# VOLTAGE_MEASURE.net
KiCad netlist of a schematic drawn in Altium Designer
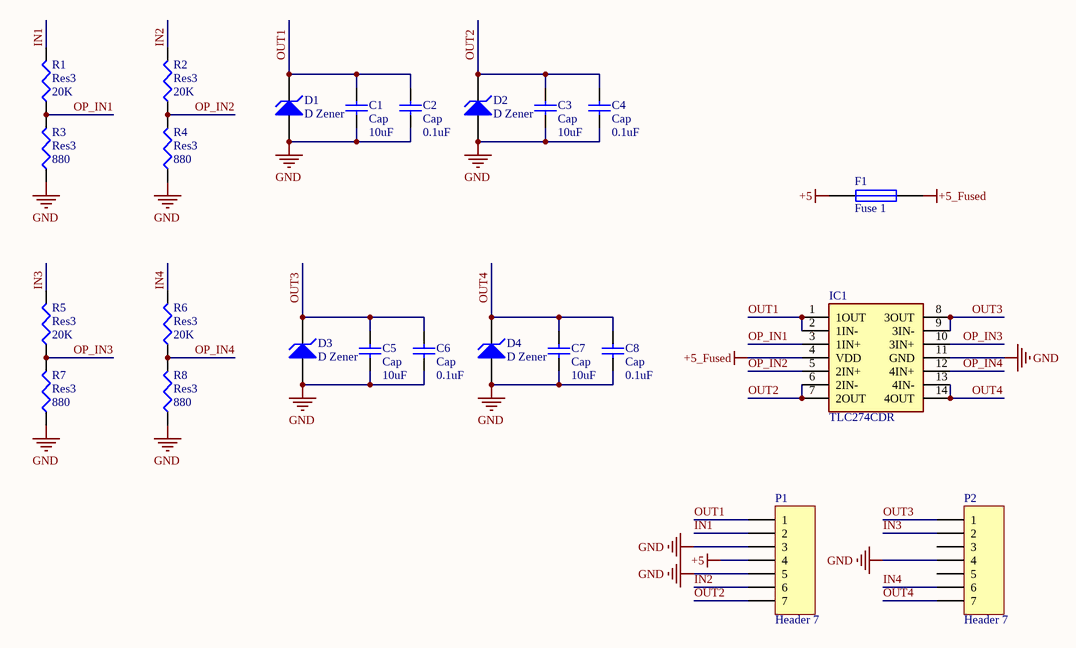
[diagram p0: VOLTAGE_MEASURE.SchDoc]

(export (version "E")
  (design (tool "Eeschema 10.0.6"))
  (components
    (comp (ref "C1")
      (value "Cap")
      (footprint "C1206")
      (description "Capacitor")
      (fields (field (name "ALTIUM_VALUE") "10uF") (field (name "PUBLISHER") "Altium Limited"))
      (libsource (lib "Miscellaneous Devices") (part "Cap"))
    )
    (comp (ref "C2")
      (value "Cap")
      (footprint "1608[0603]")
      (description "Capacitor")
      (fields (field (name "ALTIUM_VALUE") "0.1uF") (field (name "PUBLISHER") "Altium Limited"))
      (libsource (lib "Miscellaneous Devices") (part "Cap"))
    )
    (comp (ref "C3")
      (value "Cap")
      (footprint "C1206")
      (description "Capacitor")
      (fields (field (name "ALTIUM_VALUE") "10uF") (field (name "PUBLISHER") "Altium Limited"))
      (libsource (lib "Miscellaneous Devices") (part "Cap"))
    )
    (comp (ref "C4")
      (value "Cap")
      (footprint "1608[0603]")
      (description "Capacitor")
      (fields (field (name "ALTIUM_VALUE") "0.1uF") (field (name "PUBLISHER") "Altium Limited"))
      (libsource (lib "Miscellaneous Devices") (part "Cap"))
    )
    (comp (ref "C5")
      (value "Cap")
      (footprint "C1206")
      (description "Capacitor")
      (fields (field (name "ALTIUM_VALUE") "10uF") (field (name "PUBLISHER") "Altium Limited"))
      (libsource (lib "Miscellaneous Devices") (part "Cap"))
    )
    (comp (ref "C6")
      (value "Cap")
      (footprint "1608[0603]")
      (description "Capacitor")
      (fields (field (name "ALTIUM_VALUE") "0.1uF") (field (name "PUBLISHER") "Altium Limited"))
      (libsource (lib "Miscellaneous Devices") (part "Cap"))
    )
    (comp (ref "C7")
      (value "Cap")
      (footprint "C1206")
      (description "Capacitor")
      (fields (field (name "ALTIUM_VALUE") "10uF") (field (name "PUBLISHER") "Altium Limited"))
      (libsource (lib "Miscellaneous Devices") (part "Cap"))
    )
    (comp (ref "C8")
      (value "Cap")
      (footprint "1608[0603]")
      (description "Capacitor")
      (fields (field (name "ALTIUM_VALUE") "0.1uF") (field (name "PUBLISHER") "Altium Limited"))
      (libsource (lib "Miscellaneous Devices") (part "Cap"))
    )
    (comp (ref "D1")
      (value "D Zener")
      (footprint "C1206")
      (description "Zener Diode")
      (fields (field (name "PUBLISHER") "Altium Limited"))
      (libsource (lib "Miscellaneous Devices") (part "D Zener"))
    )
    (comp (ref "D2")
      (value "D Zener")
      (footprint "C1206")
      (description "Zener Diode")
      (fields (field (name "PUBLISHER") "Altium Limited"))
      (libsource (lib "Miscellaneous Devices") (part "D Zener"))
    )
    (comp (ref "D3")
      (value "D Zener")
      (footprint "C1206")
      (description "Zener Diode")
      (fields (field (name "PUBLISHER") "Altium Limited"))
      (libsource (lib "Miscellaneous Devices") (part "D Zener"))
    )
    (comp (ref "D4")
      (value "D Zener")
      (footprint "C1206")
      (description "Zener Diode")
      (fields (field (name "PUBLISHER") "Altium Limited"))
      (libsource (lib "Miscellaneous Devices") (part "D Zener"))
    )
    (comp (ref "F1")
      (value "Fuse 1")
      (footprint "C1206")
      (description "Fuse")
      (fields (field (name "PUBLISHER") "Altium Limited"))
      (libsource (lib "Miscellaneous Devices") (part "Fuse 1"))
    )
    (comp (ref "IC1")
      (value "TLC274CDR")
      (footprint "SamacSys:SOIC127P600X175-14N")
      (description "Integrated Circuit")
      (fields (field (name "MOUSER PART NUMBER") "595-TLC274CDR") (field (name "RS PART NUMBER") "0527237"))
      (libsource (lib "*") (part "TLC274CDR"))
    )
    (comp (ref "P1")
      (value "Header 7")
      (footprint "HDR1X7")
      (description "Header, 7-Pin")
      (fields (field (name "PUBLISHER") "Altium Limited"))
      (libsource (lib "Miscellaneous Connectors") (part "Header 7"))
    )
    (comp (ref "P2")
      (value "Header 7")
      (footprint "HDR1X7")
      (description "Header, 7-Pin")
      (fields (field (name "PUBLISHER") "Altium Limited"))
      (libsource (lib "Miscellaneous Connectors") (part "Header 7"))
    )
    (comp (ref "R1")
      (value "Res3")
      (footprint "J1-0603")
      (description "Resistor")
      (fields (field (name "ALTIUM_VALUE") "20K") (field (name "PUBLISHER") "Altium Limited"))
      (libsource (lib "Miscellaneous Devices") (part "Res3"))
    )
    (comp (ref "R2")
      (value "Res3")
      (footprint "J1-0603")
      (description "Resistor")
      (fields (field (name "ALTIUM_VALUE") "20K") (field (name "PUBLISHER") "Altium Limited"))
      (libsource (lib "Miscellaneous Devices") (part "Res3"))
    )
    (comp (ref "R3")
      (value "Res3")
      (footprint "J1-0603")
      (description "Resistor")
      (fields (field (name "ALTIUM_VALUE") "880") (field (name "PUBLISHER") "Altium Limited"))
      (libsource (lib "Miscellaneous Devices") (part "Res3"))
    )
    (comp (ref "R4")
      (value "Res3")
      (footprint "J1-0603")
      (description "Resistor")
      (fields (field (name "ALTIUM_VALUE") "880") (field (name "PUBLISHER") "Altium Limited"))
      (libsource (lib "Miscellaneous Devices") (part "Res3"))
    )
    (comp (ref "R5")
      (value "Res3")
      (footprint "J1-0603")
      (description "Resistor")
      (fields (field (name "ALTIUM_VALUE") "20K") (field (name "PUBLISHER") "Altium Limited"))
      (libsource (lib "Miscellaneous Devices") (part "Res3"))
    )
    (comp (ref "R6")
      (value "Res3")
      (footprint "J1-0603")
      (description "Resistor")
      (fields (field (name "ALTIUM_VALUE") "20K") (field (name "PUBLISHER") "Altium Limited"))
      (libsource (lib "Miscellaneous Devices") (part "Res3"))
    )
    (comp (ref "R7")
      (value "Res3")
      (footprint "J1-0603")
      (description "Resistor")
      (fields (field (name "ALTIUM_VALUE") "880") (field (name "PUBLISHER") "Altium Limited"))
      (libsource (lib "Miscellaneous Devices") (part "Res3"))
    )
    (comp (ref "R8")
      (value "Res3")
      (footprint "J1-0603")
      (description "Resistor")
      (fields (field (name "ALTIUM_VALUE") "880") (field (name "PUBLISHER") "Altium Limited"))
      (libsource (lib "Miscellaneous Devices") (part "Res3"))
    )
  )
  (nets
    (net (code "1") (name "+5") (class "Default")
      (node (ref "F1") (pin "2") (pinfunction "2_2") (pintype "passive"))
      (node (ref "P1") (pin "4") (pinfunction "4_4") (pintype "passive"))
    )
    (net (code "2") (name "+5_Fused") (class "Default")
      (node (ref "F1") (pin "1") (pinfunction "1_1") (pintype "passive"))
      (node (ref "IC1") (pin "4") (pinfunction "VDD_4") (pintype "passive"))
    )
    (net (code "3") (name "/IN1") (class "Default")
      (node (ref "P1") (pin "2") (pinfunction "2_2") (pintype "passive"))
      (node (ref "R1") (pin "2") (pinfunction "2_2") (pintype "passive"))
    )
    (net (code "4") (name "/IN2") (class "Default")
      (node (ref "P1") (pin "6") (pinfunction "6_6") (pintype "passive"))
      (node (ref "R2") (pin "2") (pinfunction "2_2") (pintype "passive"))
    )
    (net (code "5") (name "/IN3") (class "Default")
      (node (ref "P2") (pin "2") (pinfunction "2_2") (pintype "passive"))
      (node (ref "R5") (pin "2") (pinfunction "2_2") (pintype "passive"))
    )
    (net (code "6") (name "/IN4") (class "Default")
      (node (ref "P2") (pin "6") (pinfunction "6_6") (pintype "passive"))
      (node (ref "R6") (pin "2") (pinfunction "2_2") (pintype "passive"))
    )
    (net (code "7") (name "/OP_IN1") (class "Default")
      (node (ref "IC1") (pin "3") (pinfunction "1IN+_3") (pintype "passive"))
      (node (ref "R1") (pin "1") (pinfunction "1_1") (pintype "passive"))
      (node (ref "R3") (pin "2") (pinfunction "2_2") (pintype "passive"))
    )
    (net (code "8") (name "/OP_IN2") (class "Default")
      (node (ref "IC1") (pin "5") (pinfunction "2IN+_5") (pintype "passive"))
      (node (ref "R2") (pin "1") (pinfunction "1_1") (pintype "passive"))
      (node (ref "R4") (pin "2") (pinfunction "2_2") (pintype "passive"))
    )
    (net (code "9") (name "/OP_IN3") (class "Default")
      (node (ref "IC1") (pin "10") (pinfunction "3IN+_10") (pintype "passive"))
      (node (ref "R5") (pin "1") (pinfunction "1_1") (pintype "passive"))
      (node (ref "R7") (pin "2") (pinfunction "2_2") (pintype "passive"))
    )
    (net (code "10") (name "/OP_IN4") (class "Default")
      (node (ref "IC1") (pin "12") (pinfunction "4IN+_12") (pintype "passive"))
      (node (ref "R6") (pin "1") (pinfunction "1_1") (pintype "passive"))
      (node (ref "R8") (pin "2") (pinfunction "2_2") (pintype "passive"))
    )
    (net (code "11") (name "/OUT1") (class "Default")
      (node (ref "C1") (pin "2") (pinfunction "2_2") (pintype "passive"))
      (node (ref "C2") (pin "2") (pinfunction "2_2") (pintype "passive"))
      (node (ref "D1") (pin "2") (pinfunction "K_2") (pintype "passive"))
      (node (ref "IC1") (pin "1") (pinfunction "1OUT_1") (pintype "passive"))
      (node (ref "IC1") (pin "2") (pinfunction "1IN-_2") (pintype "passive"))
      (node (ref "P1") (pin "1") (pinfunction "1_1") (pintype "passive"))
    )
    (net (code "12") (name "/OUT2") (class "Default")
      (node (ref "C3") (pin "2") (pinfunction "2_2") (pintype "passive"))
      (node (ref "C4") (pin "2") (pinfunction "2_2") (pintype "passive"))
      (node (ref "D2") (pin "2") (pinfunction "K_2") (pintype "passive"))
      (node (ref "IC1") (pin "6") (pinfunction "2IN-_6") (pintype "passive"))
      (node (ref "IC1") (pin "7") (pinfunction "2OUT_7") (pintype "passive"))
      (node (ref "P1") (pin "7") (pinfunction "7_7") (pintype "passive"))
    )
    (net (code "13") (name "/OUT3") (class "Default")
      (node (ref "C5") (pin "2") (pinfunction "2_2") (pintype "passive"))
      (node (ref "C6") (pin "2") (pinfunction "2_2") (pintype "passive"))
      (node (ref "D3") (pin "2") (pinfunction "K_2") (pintype "passive"))
      (node (ref "IC1") (pin "8") (pinfunction "3OUT_8") (pintype "passive"))
      (node (ref "IC1") (pin "9") (pinfunction "3IN-_9") (pintype "passive"))
      (node (ref "P2") (pin "1") (pinfunction "1_1") (pintype "passive"))
    )
    (net (code "14") (name "/OUT4") (class "Default")
      (node (ref "C7") (pin "2") (pinfunction "2_2") (pintype "passive"))
      (node (ref "C8") (pin "2") (pinfunction "2_2") (pintype "passive"))
      (node (ref "D4") (pin "2") (pinfunction "K_2") (pintype "passive"))
      (node (ref "IC1") (pin "13") (pinfunction "4IN-_13") (pintype "passive"))
      (node (ref "IC1") (pin "14") (pinfunction "4OUT_14") (pintype "passive"))
      (node (ref "P2") (pin "7") (pinfunction "7_7") (pintype "passive"))
    )
    (net (code "15") (name "GND") (class "Default")
      (node (ref "C1") (pin "1") (pinfunction "1_1") (pintype "passive"))
      (node (ref "C2") (pin "1") (pinfunction "1_1") (pintype "passive"))
      (node (ref "C3") (pin "1") (pinfunction "1_1") (pintype "passive"))
      (node (ref "C4") (pin "1") (pinfunction "1_1") (pintype "passive"))
      (node (ref "C5") (pin "1") (pinfunction "1_1") (pintype "passive"))
      (node (ref "C6") (pin "1") (pinfunction "1_1") (pintype "passive"))
      (node (ref "C7") (pin "1") (pinfunction "1_1") (pintype "passive"))
      (node (ref "C8") (pin "1") (pinfunction "1_1") (pintype "passive"))
      (node (ref "D1") (pin "1") (pinfunction "A_1") (pintype "passive"))
      (node (ref "D2") (pin "1") (pinfunction "A_1") (pintype "passive"))
      (node (ref "D3") (pin "1") (pinfunction "A_1") (pintype "passive"))
      (node (ref "D4") (pin "1") (pinfunction "A_1") (pintype "passive"))
      (node (ref "IC1") (pin "11") (pinfunction "GND_11") (pintype "passive"))
      (node (ref "P1") (pin "3") (pinfunction "3_3") (pintype "passive"))
      (node (ref "P1") (pin "5") (pinfunction "5_5") (pintype "passive"))
      (node (ref "P2") (pin "4") (pinfunction "4_4") (pintype "passive"))
      (node (ref "R3") (pin "1") (pinfunction "1_1") (pintype "passive"))
      (node (ref "R4") (pin "1") (pinfunction "1_1") (pintype "passive"))
      (node (ref "R7") (pin "1") (pinfunction "1_1") (pintype "passive"))
      (node (ref "R8") (pin "1") (pinfunction "1_1") (pintype "passive"))
    )
    (net (code "16") (name "unconnected-(P2-Pad3)") (class "Default")
      (node (ref "P2") (pin "3") (pinfunction "3_3") (pintype "passive"))
    )
    (net (code "17") (name "unconnected-(P2-Pad5)") (class "Default")
      (node (ref "P2") (pin "5") (pinfunction "5_5") (pintype "passive"))
    )
  )
)
